# MCU.net
KiCad netlist of a schematic drawn in Altium Designer
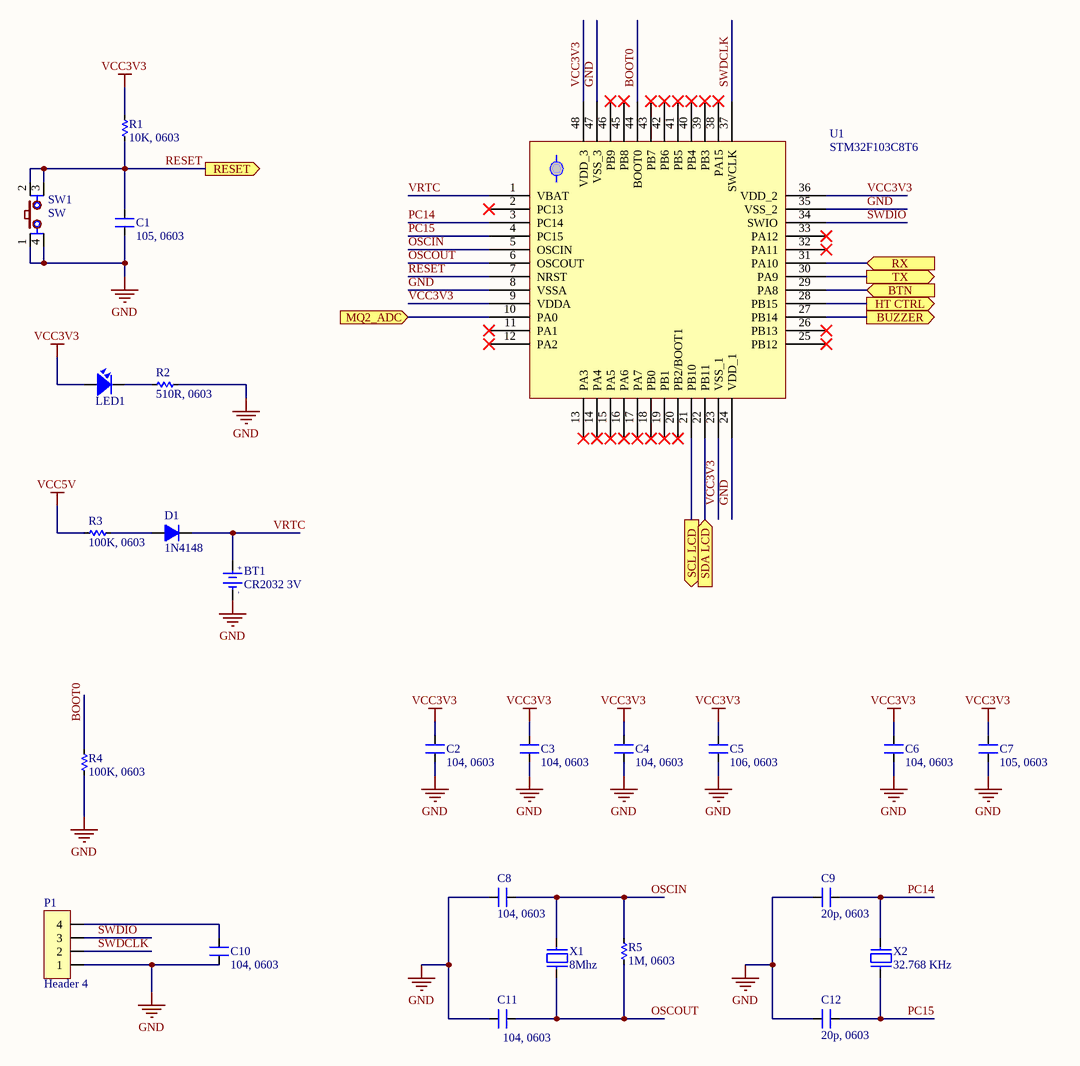
[diagram p0: MCU.SchDoc]

(export (version "E")
  (design (tool "Eeschema 10.0.6"))
  (components
    (comp (ref "BT1")
      (value "CR2032 3V")
      (footprint "PIN3V")
      (description "CR2032 3VDC rechargeable")
      (libsource (lib "KhanhBK_SCH_Library_1") (part "PIN 3V"))
    )
    (comp (ref "C1")
      (value "105, 0603")
      (footprint "SM-0603")
      (description "Cap SMD")
      (libsource (lib "KhanhBK_Library_4") (part "CM"))
    )
    (comp (ref "C2")
      (value "104, 0603")
      (footprint "SM-0603")
      (description "Cap SMD")
      (libsource (lib "KhanhBK_Library_4") (part "CM"))
    )
    (comp (ref "C3")
      (value "104, 0603")
      (footprint "SM-0603")
      (description "Cap SMD")
      (libsource (lib "KhanhBK_Library_4") (part "CM"))
    )
    (comp (ref "C4")
      (value "104, 0603")
      (footprint "SM-0603")
      (description "Cap SMD")
      (libsource (lib "KhanhBK_Library_4") (part "CM"))
    )
    (comp (ref "C5")
      (value "106, 0603")
      (footprint "SM-0603")
      (description "Cap SMD")
      (libsource (lib "KhanhBK_Library_4") (part "CM"))
    )
    (comp (ref "C6")
      (value "104, 0603")
      (footprint "SM-0603")
      (description "Cap SMD")
      (libsource (lib "KhanhBK_Library_4") (part "CM"))
    )
    (comp (ref "C7")
      (value "105, 0603")
      (footprint "SM-0603")
      (description "Cap SMD")
      (libsource (lib "KhanhBK_Library_4") (part "CM"))
    )
    (comp (ref "C8")
      (value "104, 0603")
      (footprint "SM-0603")
      (description "Cap SMD")
      (libsource (lib "KhanhBK_Library_4") (part "CM"))
    )
    (comp (ref "C9")
      (value "20p, 0603")
      (footprint "SM-0603")
      (description "Cap SMD")
      (libsource (lib "KhanhBK_Library_4") (part "CM"))
    )
    (comp (ref "C10")
      (value "104, 0603")
      (footprint "SM-0603")
      (description "Cap SMD")
      (libsource (lib "KhanhBK_Library_4") (part "CM"))
    )
    (comp (ref "C11")
      (value "104, 0603")
      (footprint "SM-0603")
      (description "Cap SMD")
      (libsource (lib "KhanhBK_Library_4") (part "CM"))
    )
    (comp (ref "C12")
      (value "20p, 0603")
      (footprint "SM-0603")
      (description "Cap SMD")
      (libsource (lib "KhanhBK_Library_4") (part "CM"))
    )
    (comp (ref "D1")
      (value "1N4148")
      (footprint "D0.5A")
      (description "D0.5A")
      (libsource (lib "KhanhBK_SCH_Library_2") (part "D0.5A"))
    )
    (comp (ref "LED1")
      (value "LED")
      (footprint "LED-0805-Blue")
      (libsource (lib "KhanhBK_SCH_Library_1") (part "LED SMD"))
    )
    (comp (ref "P1")
      (value "Header 4")
      (footprint "HDR/Header/4")
      (description "Header, 4-Pin")
      (libsource (lib "connectors") (part "Header 4"))
    )
    (comp (ref "R1")
      (value "10K, 0603")
      (footprint "RES-SMD-0603")
      (description "Resistor")
      (fields
        (field (name "MANUFACTURER") "Generic Components")
        (field (name "PUBLISHER") "Altium Hobart Technology Centre")
      )
      (libsource (lib "KhanhBK_SCH_Library_1") (part "Res-SMD"))
    )
    (comp (ref "R2")
      (value "510R, 0603")
      (footprint "RES-SMD-0603")
      (description "Resistor")
      (fields
        (field (name "MANUFACTURER") "Generic Components")
        (field (name "PUBLISHER") "Altium Hobart Technology Centre")
      )
      (libsource (lib "KhanhBK_SCH_Library_1") (part "Res-SMD"))
    )
    (comp (ref "R3")
      (value "100K, 0603")
      (footprint "RES-SMD-0603")
      (description "Resistor")
      (fields
        (field (name "MANUFACTURER") "Generic Components")
        (field (name "PUBLISHER") "Altium Hobart Technology Centre")
      )
      (libsource (lib "KhanhBK_SCH_Library_1") (part "Res-SMD"))
    )
    (comp (ref "R4")
      (value "100K, 0603")
      (footprint "RES-SMD-0603")
      (description "Resistor")
      (fields
        (field (name "MANUFACTURER") "Generic Components")
        (field (name "PUBLISHER") "Altium Hobart Technology Centre")
      )
      (libsource (lib "KhanhBK_SCH_Library_1") (part "Res-SMD"))
    )
    (comp (ref "R5")
      (value "1M, 0603")
      (footprint "RES-SMD-0603")
      (description "Resistor")
      (fields
        (field (name "MANUFACTURER") "Generic Components")
        (field (name "PUBLISHER") "Altium Hobart Technology Centre")
      )
      (libsource (lib "KhanhBK_SCH_Library_1") (part "Res-SMD"))
    )
    (comp (ref "SW1")
      (value "SW")
      (footprint "SW2-SMD")
      (description "Switch button 4 pin")
      (libsource (lib "KhanhBK_SCH_Library_1") (part "SW4"))
    )
    (comp (ref "U1")
      (value "STM32F103C8T6")
      (footprint "QFP50P900X900X160-48N")
      (libsource (lib "Project2_Library") (part "STM32F103C8T6"))
    )
    (comp (ref "X1")
      (value "8Mhz")
      (footprint "XT2")
      (description "Crystal For all Crystal 2pin.")
      (libsource (lib "KhanhBK_SCH_Library_2") (part "XT2"))
    )
    (comp (ref "X2")
      (value "32.768 KHz")
      (footprint "XT2-SMD")
      (description "Crystal, 32.768 KHz, -40 to 85 degC, 3.2 x 1.5 x 0.9 mm SMD")
      (libsource (lib "KhanhBK_SCH_Library_1") (part "XT2"))
    )
  )
  (nets
    (net (code "1") (name "/BOOT0") (class "Default")
      (node (ref "R4") (pin "1") (pinfunction "1_1") (pintype "passive"))
      (node (ref "U1") (pin "44") (pinfunction "BOOT0_44") (pintype "passive"))
    )
    (net (code "2") (name "/BTN") (class "Default")
      (node (ref "U1") (pin "29") (pinfunction "PA8_29") (pintype "passive"))
    )
    (net (code "3") (name "/BUZZER") (class "Default")
      (node (ref "U1") (pin "27") (pinfunction "PB14_27") (pintype "passive"))
    )
    (net (code "4") (name "/HT CTRL") (class "Default")
      (node (ref "U1") (pin "28") (pinfunction "PB15_28") (pintype "passive"))
    )
    (net (code "5") (name "/MQ2_ADC") (class "Default")
      (node (ref "U1") (pin "10") (pinfunction "PA0_10") (pintype "passive"))
    )
    (net (code "6") (name "/OSCIN") (class "Default")
      (node (ref "C8") (pin "2") (pinfunction "2_2") (pintype "passive"))
      (node (ref "R5") (pin "1") (pinfunction "1_1") (pintype "passive"))
      (node (ref "U1") (pin "5") (pinfunction "OSCIN_5") (pintype "passive"))
      (node (ref "X1") (pin "2") (pinfunction "2_2") (pintype "passive"))
    )
    (net (code "7") (name "/OSCOUT") (class "Default")
      (node (ref "C11") (pin "1") (pinfunction "1_1") (pintype "passive"))
      (node (ref "R5") (pin "2") (pinfunction "2_2") (pintype "passive"))
      (node (ref "U1") (pin "6") (pinfunction "OSCOUT_6") (pintype "passive"))
      (node (ref "X1") (pin "1") (pinfunction "1_1") (pintype "passive"))
    )
    (net (code "8") (name "/PC14") (class "Default")
      (node (ref "C9") (pin "1") (pinfunction "1_1") (pintype "passive"))
      (node (ref "U1") (pin "3") (pinfunction "PC14_3") (pintype "passive"))
      (node (ref "X2") (pin "2") (pinfunction "2_2") (pintype "passive"))
    )
    (net (code "9") (name "/PC15") (class "Default")
      (node (ref "C12") (pin "1") (pinfunction "1_1") (pintype "passive"))
      (node (ref "U1") (pin "4") (pinfunction "PC15_4") (pintype "passive"))
      (node (ref "X2") (pin "1") (pinfunction "1_1") (pintype "passive"))
    )
    (net (code "10") (name "/RESET") (class "Default")
      (node (ref "C1") (pin "2") (pinfunction "2_2") (pintype "passive"))
      (node (ref "R1") (pin "1") (pinfunction "1_1") (pintype "passive"))
      (node (ref "SW1") (pin "2") (pinfunction "2_2") (pintype "passive"))
      (node (ref "SW1") (pin "3") (pinfunction "3_3") (pintype "passive"))
      (node (ref "U1") (pin "7") (pinfunction "NRST_7") (pintype "passive"))
    )
    (net (code "11") (name "/RX") (class "Default")
      (node (ref "U1") (pin "31") (pinfunction "PA10_31") (pintype "passive"))
    )
    (net (code "12") (name "/SCL LCD") (class "Default")
      (node (ref "U1") (pin "21") (pinfunction "PB10_21") (pintype "passive"))
    )
    (net (code "13") (name "/SDA LCD") (class "Default")
      (node (ref "U1") (pin "22") (pinfunction "PB11_22") (pintype "passive"))
    )
    (net (code "14") (name "/SWDCLK") (class "Default")
      (node (ref "P1") (pin "2") (pinfunction "2_2") (pintype "passive"))
      (node (ref "U1") (pin "37") (pinfunction "SWCLK_37") (pintype "passive"))
    )
    (net (code "15") (name "/SWDIO") (class "Default")
      (node (ref "P1") (pin "3") (pinfunction "3_3") (pintype "passive"))
      (node (ref "U1") (pin "34") (pinfunction "SWIO_34") (pintype "passive"))
    )
    (net (code "16") (name "/TX") (class "Default")
      (node (ref "U1") (pin "30") (pinfunction "PA9_30") (pintype "passive"))
    )
    (net (code "17") (name "/VRTC") (class "Default")
      (node (ref "BT1") (pin "1") (pinfunction "+3V_1") (pintype "passive"))
      (node (ref "D1") (pin "2") (pinfunction "K_2") (pintype "passive"))
      (node (ref "U1") (pin "1") (pinfunction "VBAT_1") (pintype "passive"))
    )
    (net (code "18") (name "GND") (class "Default")
      (node (ref "BT1") (pin "2") (pinfunction "GND_2") (pintype "passive"))
      (node (ref "C1") (pin "1") (pinfunction "1_1") (pintype "passive"))
      (node (ref "C10") (pin "1") (pinfunction "1_1") (pintype "passive"))
      (node (ref "C11") (pin "2") (pinfunction "2_2") (pintype "passive"))
      (node (ref "C12") (pin "2") (pinfunction "2_2") (pintype "passive"))
      (node (ref "C2") (pin "1") (pinfunction "1_1") (pintype "passive"))
      (node (ref "C3") (pin "1") (pinfunction "1_1") (pintype "passive"))
      (node (ref "C4") (pin "1") (pinfunction "1_1") (pintype "passive"))
      (node (ref "C5") (pin "1") (pinfunction "1_1") (pintype "passive"))
      (node (ref "C6") (pin "1") (pinfunction "1_1") (pintype "passive"))
      (node (ref "C7") (pin "1") (pinfunction "1_1") (pintype "passive"))
      (node (ref "C8") (pin "1") (pinfunction "1_1") (pintype "passive"))
      (node (ref "C9") (pin "2") (pinfunction "2_2") (pintype "passive"))
      (node (ref "P1") (pin "1") (pinfunction "1_1") (pintype "passive"))
      (node (ref "R2") (pin "2") (pinfunction "2_2") (pintype "passive"))
      (node (ref "R4") (pin "2") (pinfunction "2_2") (pintype "passive"))
      (node (ref "SW1") (pin "1") (pintype "passive"))
      (node (ref "SW1") (pin "4") (pinfunction "4_4") (pintype "passive"))
      (node (ref "U1") (pin "24") (pinfunction "VDD_1_24") (pintype "passive"))
      (node (ref "U1") (pin "35") (pinfunction "VSS_2_35") (pintype "passive"))
      (node (ref "U1") (pin "47") (pinfunction "VSS_3_47") (pintype "passive"))
      (node (ref "U1") (pin "8") (pinfunction "VSSA_8") (pintype "passive"))
    )
    (net (code "19") (name "Net-(C10-Pad2)") (class "Default")
      (node (ref "C10") (pin "2") (pinfunction "2_2") (pintype "passive"))
      (node (ref "P1") (pin "4") (pinfunction "4_4") (pintype "passive"))
    )
    (net (code "20") (name "Net-(D1-A)") (class "Default")
      (node (ref "D1") (pin "1") (pinfunction "A_1") (pintype "passive"))
      (node (ref "R3") (pin "2") (pinfunction "2_2") (pintype "passive"))
    )
    (net (code "21") (name "Net-(LED1-Pad2)") (class "Default")
      (node (ref "LED1") (pin "2") (pinfunction "2_2") (pintype "passive"))
      (node (ref "R2") (pin "1") (pinfunction "1_1") (pintype "passive"))
    )
    (net (code "22") (name "VCC3V3") (class "Default")
      (node (ref "C2") (pin "2") (pinfunction "2_2") (pintype "passive"))
      (node (ref "C3") (pin "2") (pinfunction "2_2") (pintype "passive"))
      (node (ref "C4") (pin "2") (pinfunction "2_2") (pintype "passive"))
      (node (ref "C5") (pin "2") (pinfunction "2_2") (pintype "passive"))
      (node (ref "C6") (pin "2") (pinfunction "2_2") (pintype "passive"))
      (node (ref "C7") (pin "2") (pinfunction "2_2") (pintype "passive"))
      (node (ref "LED1") (pin "1") (pinfunction "1_1") (pintype "passive"))
      (node (ref "R1") (pin "2") (pinfunction "2_2") (pintype "passive"))
      (node (ref "U1") (pin "23") (pinfunction "VSS_1_23") (pintype "passive"))
      (node (ref "U1") (pin "36") (pinfunction "VDD_2_36") (pintype "passive"))
      (node (ref "U1") (pin "48") (pinfunction "VDD_3_48") (pintype "passive"))
      (node (ref "U1") (pin "9") (pinfunction "VDDA_9") (pintype "passive"))
    )
    (net (code "23") (name "VCC5V") (class "Default")
      (node (ref "R3") (pin "1") (pinfunction "1_1") (pintype "passive"))
    )
    (net (code "24") (name "unconnected-(U1-PA1-Pad11)") (class "Default")
      (node (ref "U1") (pin "11") (pinfunction "PA1_11") (pintype "passive+no_connect"))
    )
    (net (code "25") (name "unconnected-(U1-PA2-Pad12)") (class "Default")
      (node (ref "U1") (pin "12") (pinfunction "PA2_12") (pintype "passive+no_connect"))
    )
    (net (code "26") (name "unconnected-(U1-PA3-Pad13)") (class "Default")
      (node (ref "U1") (pin "13") (pinfunction "PA3_13") (pintype "passive+no_connect"))
    )
    (net (code "27") (name "unconnected-(U1-PA4-Pad14)") (class "Default")
      (node (ref "U1") (pin "14") (pinfunction "PA4_14") (pintype "passive+no_connect"))
    )
    (net (code "28") (name "unconnected-(U1-PA5-Pad15)") (class "Default")
      (node (ref "U1") (pin "15") (pinfunction "PA5_15") (pintype "passive+no_connect"))
    )
    (net (code "29") (name "unconnected-(U1-PA6-Pad16)") (class "Default")
      (node (ref "U1") (pin "16") (pinfunction "PA6_16") (pintype "passive+no_connect"))
    )
    (net (code "30") (name "unconnected-(U1-PA7-Pad17)") (class "Default")
      (node (ref "U1") (pin "17") (pinfunction "PA7_17") (pintype "passive+no_connect"))
    )
    (net (code "31") (name "unconnected-(U1-PA11-Pad32)") (class "Default")
      (node (ref "U1") (pin "32") (pinfunction "PA11_32") (pintype "passive+no_connect"))
    )
    (net (code "32") (name "unconnected-(U1-PA12-Pad33)") (class "Default")
      (node (ref "U1") (pin "33") (pinfunction "PA12_33") (pintype "passive+no_connect"))
    )
    (net (code "33") (name "unconnected-(U1-PA15-Pad38)") (class "Default")
      (node (ref "U1") (pin "38") (pinfunction "PA15_38") (pintype "passive+no_connect"))
    )
    (net (code "34") (name "unconnected-(U1-PB0-Pad18)") (class "Default")
      (node (ref "U1") (pin "18") (pinfunction "PB0_18") (pintype "passive+no_connect"))
    )
    (net (code "35") (name "unconnected-(U1-PB1-Pad19)") (class "Default")
      (node (ref "U1") (pin "19") (pinfunction "PB1_19") (pintype "passive+no_connect"))
    )
    (net (code "36") (name "unconnected-(U1-PB2{slash}BOOT1-Pad20)") (class "Default")
      (node (ref "U1") (pin "20") (pinfunction "PB2/BOOT1_20") (pintype "passive+no_connect"))
    )
    (net (code "37") (name "unconnected-(U1-PB3-Pad39)") (class "Default")
      (node (ref "U1") (pin "39") (pinfunction "PB3_39") (pintype "passive+no_connect"))
    )
    (net (code "38") (name "unconnected-(U1-PB4-Pad40)") (class "Default")
      (node (ref "U1") (pin "40") (pinfunction "PB4_40") (pintype "passive+no_connect"))
    )
    (net (code "39") (name "unconnected-(U1-PB5-Pad41)") (class "Default")
      (node (ref "U1") (pin "41") (pinfunction "PB5_41") (pintype "passive+no_connect"))
    )
    (net (code "40") (name "unconnected-(U1-PB6-Pad42)") (class "Default")
      (node (ref "U1") (pin "42") (pinfunction "PB6_42") (pintype "passive+no_connect"))
    )
    (net (code "41") (name "unconnected-(U1-PB7-Pad43)") (class "Default")
      (node (ref "U1") (pin "43") (pinfunction "PB7_43") (pintype "passive+no_connect"))
    )
    (net (code "42") (name "unconnected-(U1-PB8-Pad45)") (class "Default")
      (node (ref "U1") (pin "45") (pinfunction "PB8_45") (pintype "passive+no_connect"))
    )
    (net (code "43") (name "unconnected-(U1-PB9-Pad46)") (class "Default")
      (node (ref "U1") (pin "46") (pinfunction "PB9_46") (pintype "passive+no_connect"))
    )
    (net (code "44") (name "unconnected-(U1-PB12-Pad25)") (class "Default")
      (node (ref "U1") (pin "25") (pinfunction "PB12_25") (pintype "passive+no_connect"))
    )
    (net (code "45") (name "unconnected-(U1-PB13-Pad26)") (class "Default")
      (node (ref "U1") (pin "26") (pinfunction "PB13_26") (pintype "passive+no_connect"))
    )
    (net (code "46") (name "unconnected-(U1-PC13-Pad2)") (class "Default")
      (node (ref "U1") (pin "2") (pinfunction "PC13_2") (pintype "passive+no_connect"))
    )
  )
)
